# power.net
KiCad netlist of a schematic drawn in Altium Designer
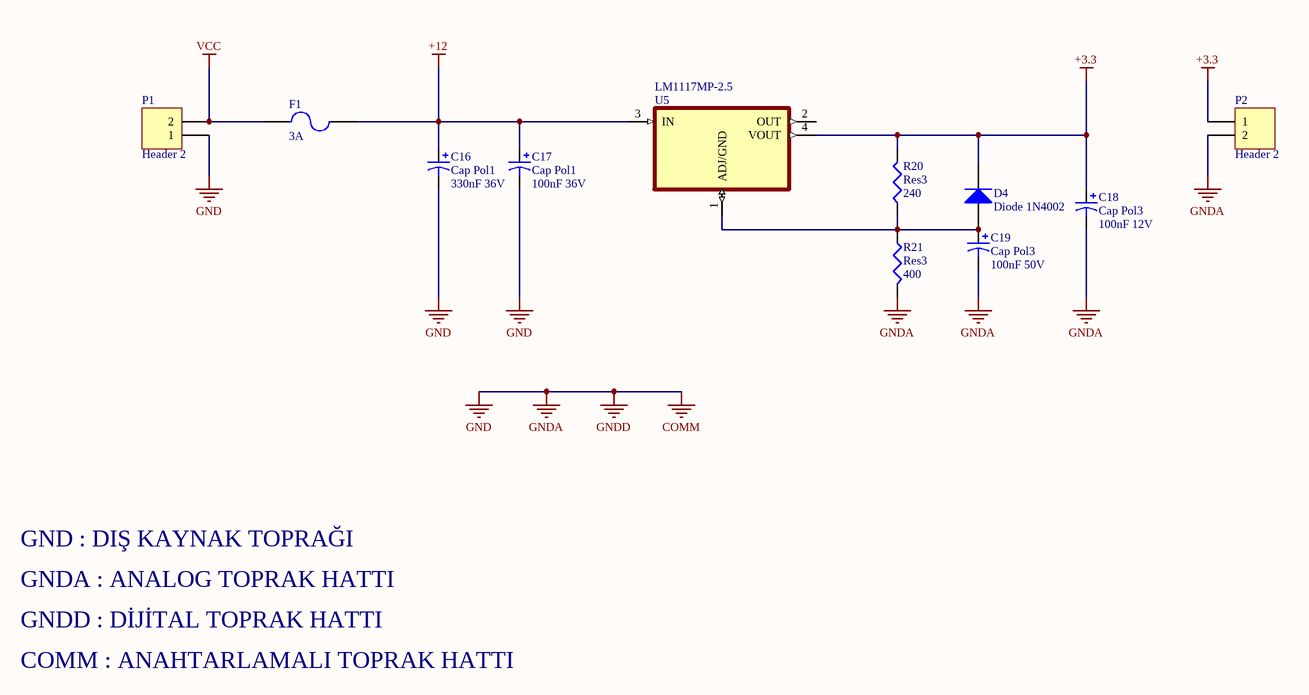
[diagram p0: power.SchDoc]

(export (version "E")
  (design (tool "Eeschema 10.0.6"))
  (components
    (comp (ref "C16")
      (value "Cap Pol1")
      (footprint "RB7.6-15")
      (description "Polarized Capacitor (Radial)")
      (fields (field (name "ALTIUM_VALUE") "330nF 36V") (field (name "PUBLISHER") "Altium Limited"))
      (libsource (lib "Miscellaneous Devices") (part "Cap Pol1"))
    )
    (comp (ref "C17")
      (value "Cap Pol1")
      (footprint "RB7.6-15")
      (description "Polarized Capacitor (Radial)")
      (fields (field (name "ALTIUM_VALUE") "100nF 36V") (field (name "PUBLISHER") "Altium Limited"))
      (libsource (lib "Miscellaneous Devices") (part "Cap Pol1"))
    )
    (comp (ref "C18")
      (value "Cap Pol3")
      (footprint "C0805")
      (description "Polarized Capacitor (Surface Mount)")
      (fields (field (name "ALTIUM_VALUE") "100nF 12V") (field (name "PUBLISHER") "Altium Limited"))
      (libsource (lib "Miscellaneous Devices") (part "Cap Pol3"))
    )
    (comp (ref "C19")
      (value "Cap Pol3")
      (footprint "C0805")
      (description "Polarized Capacitor (Surface Mount)")
      (fields (field (name "ALTIUM_VALUE") "100nF 50V") (field (name "PUBLISHER") "Altium Limited"))
      (libsource (lib "Miscellaneous Devices") (part "Cap Pol3"))
    )
    (comp (ref "D4")
      (value "Diode 1N4002")
      (footprint "DO-41")
      (description "1 Amp General Purpose Rectifier")
      (fields (field (name "PUBLISHER") "Altium Limited"))
      (libsource (lib "Miscellaneous Devices") (part "Diode 1N4007"))
    )
    (comp (ref "F1")
      (value "3A")
      (footprint "PIN-W2/E2.8")
      (description "Fuse")
      (fields (field (name "PUBLISHER") "Altium Limited"))
      (libsource (lib "Miscellaneous Devices") (part "Fuse 2"))
    )
    (comp (ref "P1")
      (value "Header 2")
      (footprint "HDR1X2")
      (description "Header, 2-Pin")
      (fields (field (name "PUBLISHER") "Altium Limited"))
      (libsource (lib "Miscellaneous Connectors") (part "Header 2"))
    )
    (comp (ref "P2")
      (value "Header 2")
      (footprint "HDR1X2")
      (description "Header, 2-Pin")
      (fields (field (name "PUBLISHER") "Altium Limited"))
      (libsource (lib "") (part "Header 2_1"))
    )
    (comp (ref "R20")
      (value "Res3")
      (footprint "J1-0603")
      (description "Resistor")
      (fields (field (name "ALTIUM_VALUE") "240") (field (name "PUBLISHER") "Altium Limited"))
      (libsource (lib "Miscellaneous Devices") (part "Res3"))
    )
    (comp (ref "R21")
      (value "Res3")
      (footprint "J1-0603")
      (description "Resistor")
      (fields (field (name "ALTIUM_VALUE") "400") (field (name "PUBLISHER") "Altium Limited"))
      (libsource (lib "Miscellaneous Devices") (part "Res3"))
    )
    (comp (ref "U5")
      (value "LM1117MP-2.5")
      (footprint "LM1117 SMD")
      (description "800-mA 15-V linear voltage regulator 4-SOT-223 0 to 125")
      (fields (field (name "MP") "LM1117MP-2.5/NOPB") (field (name "MF") "Texas Instruments"))
      (libsource (lib "RoketAnaSistemSematikKütüphane") (part "LM1117MP-2.5"))
    )
  )
  (nets
    (net (code "1") (name "+3.3") (class "Default")
      (node (ref "C18") (pin "1") (pinfunction "1_1") (pintype "passive"))
      (node (ref "D4") (pin "2") (pinfunction "K_2") (pintype "passive"))
      (node (ref "P2") (pin "1") (pinfunction "1_1") (pintype "passive"))
      (node (ref "R20") (pin "2") (pinfunction "2_2") (pintype "passive"))
      (node (ref "U5") (pin "4") (pinfunction "VOUT_4") (pintype "output"))
    )
    (net (code "2") (name "+12") (class "Default")
      (node (ref "C16") (pin "1") (pinfunction "1_1") (pintype "passive"))
      (node (ref "C17") (pin "1") (pinfunction "1_1") (pintype "passive"))
      (node (ref "F1") (pin "2") (pinfunction "2_2") (pintype "passive"))
      (node (ref "U5") (pin "3") (pinfunction "IN_3") (pintype "input"))
    )
    (net (code "3") (name "COMM") (class "Default")
      (node (ref "C16") (pin "2") (pinfunction "2_2") (pintype "passive"))
      (node (ref "C17") (pin "2") (pinfunction "2_2") (pintype "passive"))
      (node (ref "C18") (pin "2") (pinfunction "2_2") (pintype "passive"))
      (node (ref "C19") (pin "2") (pinfunction "2_2") (pintype "passive"))
      (node (ref "P1") (pin "1") (pinfunction "1_1") (pintype "passive"))
      (node (ref "P2") (pin "2") (pinfunction "2_2") (pintype "passive"))
      (node (ref "R21") (pin "2") (pinfunction "2_2") (pintype "passive"))
    )
    (net (code "4") (name "Net-(D4-A)") (class "Default")
      (node (ref "C19") (pin "1") (pinfunction "1_1") (pintype "passive"))
      (node (ref "D4") (pin "1") (pinfunction "A_1") (pintype "passive"))
      (node (ref "R20") (pin "1") (pinfunction "1_1") (pintype "passive"))
      (node (ref "R21") (pin "1") (pinfunction "1_1") (pintype "passive"))
      (node (ref "U5") (pin "1") (pinfunction "ADJ/GND_1") (pintype "bidirectional"))
    )
    (net (code "5") (name "VCC") (class "Default")
      (node (ref "F1") (pin "1") (pinfunction "1_1") (pintype "passive"))
      (node (ref "P1") (pin "2") (pinfunction "2_2") (pintype "passive"))
    )
    (net (code "6") (name "unconnected-(U5-OUT-Pad2)") (class "Default")
      (node (ref "U5") (pin "2") (pinfunction "OUT_2") (pintype "output"))
    )
  )
)
